# Sheet1.net
KiCad netlist of a schematic drawn in Altium Designer
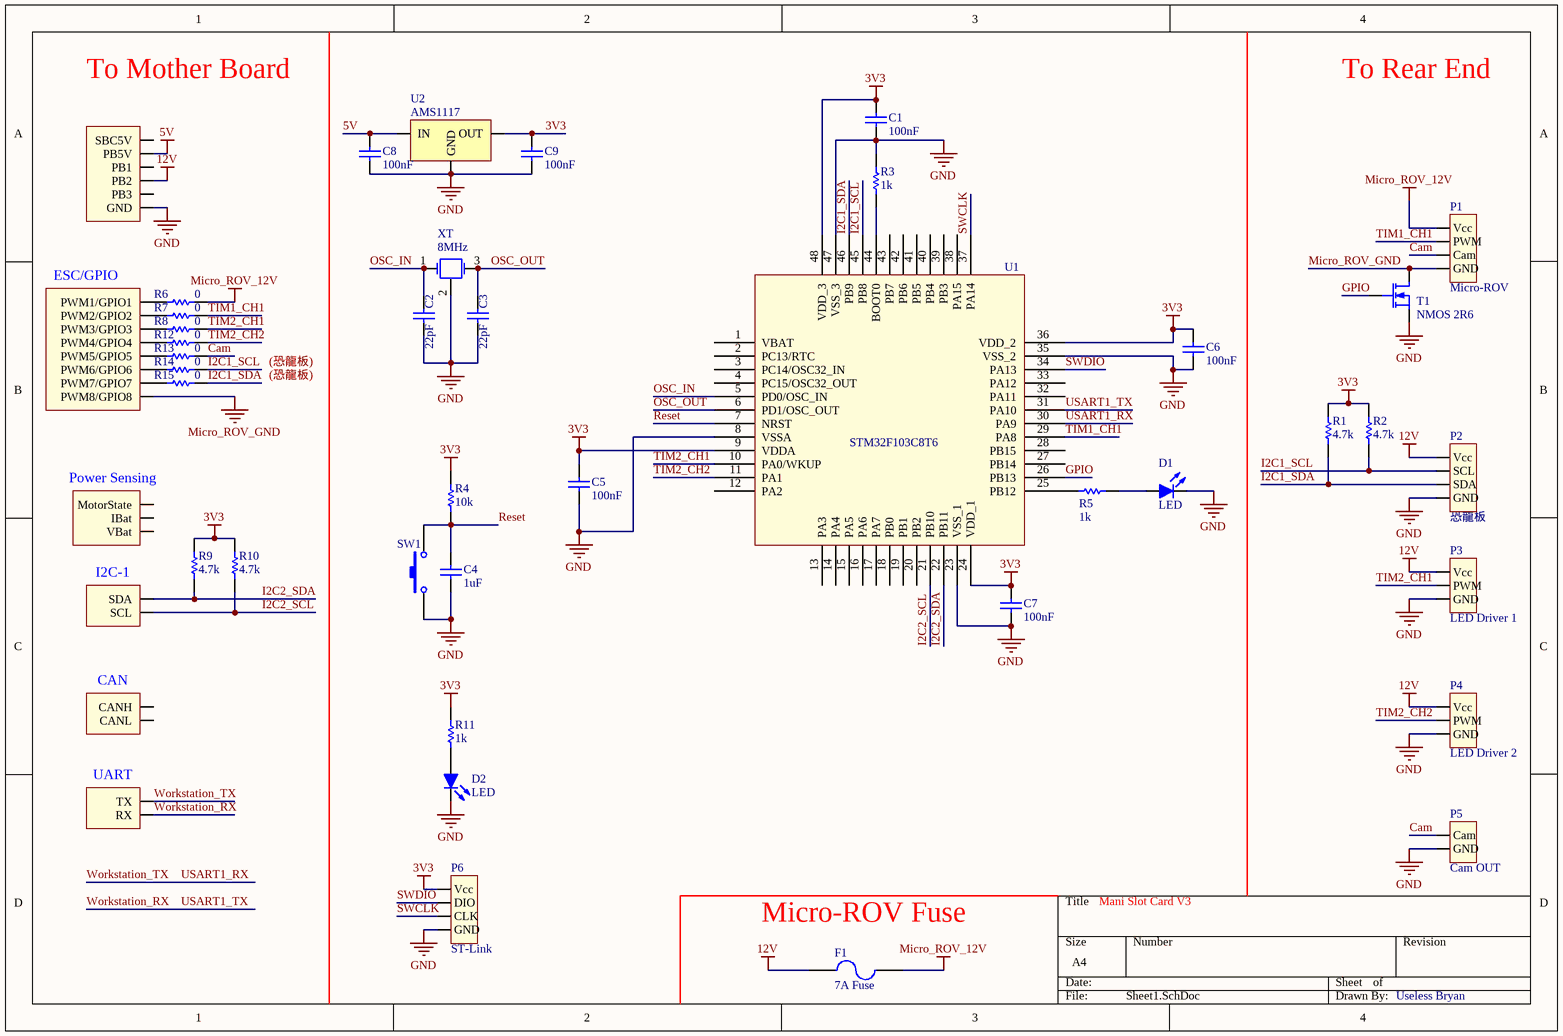
[diagram p0: Sheet1.SchDoc]

(export (version "E")
  (design (tool "Eeschema 10.0.6"))
  (components
    (comp (ref "C1") (value "100nF") (footprint "C0805") (libsource (lib "MyOwnSchlib_ver1.2") (part "Cap")))
    (comp (ref "C2") (value "22pF") (footprint "C0805") (libsource (lib "MyOwnSchlib_ver1.2") (part "Cap")))
    (comp (ref "C3") (value "22pF") (footprint "C0805") (libsource (lib "MyOwnSchlib_ver1.2") (part "Cap")))
    (comp (ref "C4") (value "1uF") (footprint "C0805") (libsource (lib "MyOwnSchlib_ver1.2") (part "Cap")))
    (comp (ref "C5") (value "100nF") (footprint "C0805") (libsource (lib "MyOwnSchlib_ver1.2") (part "Cap")))
    (comp (ref "C6") (value "100nF") (footprint "C0805") (libsource (lib "MyOwnSchlib_ver1.2") (part "Cap")))
    (comp (ref "C7") (value "100nF") (footprint "C0805") (libsource (lib "MyOwnSchlib_ver1.2") (part "Cap")))
    (comp (ref "C8") (value "100nF") (footprint "C0805") (libsource (lib "MyOwnSchlib_ver1.2") (part "Cap")))
    (comp (ref "C9") (value "100nF") (footprint "C0805") (libsource (lib "MyOwnSchlib_ver1.2") (part "Cap")))
    (comp (ref "Con1") (value "2x10pin") (footprint "2x10pin") (libsource (lib "Schlib1") (part "2x10pin")))
    (comp (ref "Con2") (value "2x6pin") (footprint "2x6pin") (libsource (lib "Schlib1") (part "2x6pin")))
    (comp (ref "D1") (value "LED") (footprint "LED-0805") (libsource (lib "MyOwnSchlib_ver1.2") (part "LED")))
    (comp (ref "D2") (value "LED") (footprint "LED-0805") (libsource (lib "MyOwnSchlib_ver1.2") (part "LED")))
    (comp (ref "F1")
      (value "7A Fuse")
      (footprint "FUSE-BLXA")
      (libsource (lib "MyOwnSchlib_ver1.2") (part "Fuse"))
    )
    (comp (ref "P1") (value "Micro-ROV") (footprint "XH2.54-4PIN_SMD") (libsource (lib "") (part "4Pin_2")))
    (comp (ref "P2")
      (value "Hung Lone V1")
      (footprint "XH2.54-4PIN_SMD")
      (libsource (lib "") (part "4Pin_1"))
    )
    (comp (ref "P3")
      (value "LED Driver 1")
      (footprint "XH2.54-3Pin_SMD")
      (libsource (lib "MyOwnSchlib_ver1.2") (part "3Pin"))
    )
    (comp (ref "P4")
      (value "LED Driver 2")
      (footprint "XH2.54-3Pin_SMD")
      (libsource (lib "MyOwnSchlib_ver1.2") (part "3Pin"))
    )
    (comp (ref "P5")
      (value "Cam OUT")
      (footprint "XH2.54-2Pin_SMD")
      (libsource (lib "MyOwnSchlib_ver1.2") (part "2Pin"))
    )
    (comp (ref "P6")
      (value "ST-Link")
      (footprint "XH2.54-4pin")
      (libsource (lib "MyOwnSchlib_ver1.2") (part "4Pin"))
    )
    (comp (ref "R1")
      (value "4.7k")
      (footprint "R0805")
      (description "pull-up resistor")
      (libsource (lib "MyOwnSchlib_ver1.2") (part "Resistor"))
    )
    (comp (ref "R2")
      (value "4.7k")
      (footprint "R0805")
      (description "pull-up resistor")
      (libsource (lib "MyOwnSchlib_ver1.2") (part "Resistor"))
    )
    (comp (ref "R3")
      (value "1k")
      (footprint "R0805")
      (libsource (lib "MyOwnSchlib_ver1.2") (part "Resistor"))
    )
    (comp (ref "R4")
      (value "10k")
      (footprint "R0805")
      (description "pull-up resistor")
      (libsource (lib "MyOwnSchlib_ver1.2") (part "Resistor"))
    )
    (comp (ref "R5")
      (value "1k")
      (footprint "R0805")
      (libsource (lib "MyOwnSchlib_ver1.2") (part "Resistor"))
    )
    (comp (ref "R6") (value "0") (footprint "R1206") (libsource (lib "MyOwnSchlib_ver1.2") (part "Resistor")))
    (comp (ref "R7") (value "0") (footprint "R0603") (libsource (lib "MyOwnSchlib_ver1.2") (part "Resistor")))
    (comp (ref "R8") (value "0") (footprint "R0603") (libsource (lib "MyOwnSchlib_ver1.2") (part "Resistor")))
    (comp (ref "R9")
      (value "4.7k")
      (footprint "R0805")
      (libsource (lib "MyOwnSchlib_ver1.2") (part "Resistor"))
    )
    (comp (ref "R10")
      (value "4.7k")
      (footprint "R0805")
      (libsource (lib "MyOwnSchlib_ver1.2") (part "Resistor"))
    )
    (comp (ref "R11")
      (value "1k")
      (footprint "R0805")
      (libsource (lib "MyOwnSchlib_ver1.2") (part "Resistor"))
    )
    (comp (ref "R12")
      (value "0")
      (footprint "R0603")
      (libsource (lib "MyOwnSchlib_ver1.2") (part "Resistor"))
    )
    (comp (ref "R13")
      (value "0")
      (footprint "R0603")
      (libsource (lib "MyOwnSchlib_ver1.2") (part "Resistor"))
    )
    (comp (ref "R14")
      (value "0")
      (footprint "R0603")
      (libsource (lib "MyOwnSchlib_ver1.2") (part "Resistor"))
    )
    (comp (ref "R15")
      (value "0")
      (footprint "R0603")
      (libsource (lib "MyOwnSchlib_ver1.2") (part "Resistor"))
    )
    (comp (ref "SW1")
      (value "SW-PB")
      (footprint "Switch-2pin")
      (libsource (lib "MyOwnSchlib_ver1.2") (part "SW-PB"))
    )
    (comp (ref "T1")
      (value "NMOS 2R6")
      (footprint "TPH2R608NH")
      (libsource (lib "convert") (part "MOSFET-N"))
    )
    (comp (ref "U1")
      (value "STM32F103C8T6")
      (footprint "LQFP48")
      (libsource (lib "MyOwnSchlib_ver1.2") (part "STM32F103C8T6"))
    )
    (comp (ref "U2")
      (value "AMS1117")
      (footprint "SOT-223")
      (libsource (lib "MyOwnSchlib_ver1.2") (part "AMS1117"))
    )
    (comp (ref "XT")
      (value "8MHz")
      (footprint "3225-P")
      (libsource (lib "MyOwnSchlib_ver1.2") (part "Passive Crystal"))
    )
  )
  (nets
    (net (code "1") (name "/Cam") (class "Default")
      (node (ref "P1") (pin "3") (pinfunction "Cam_3") (pintype "passive"))
      (node (ref "P5") (pin "1") (pinfunction "Cam_1") (pintype "passive"))
      (node (ref "R13") (pin "2") (pinfunction "2_2") (pintype "passive"))
    )
    (net (code "2") (name "/GPIO") (class "Default")
      (node (ref "T1") (pin "2") (pinfunction "G_2") (pintype "passive"))
      (node (ref "U1") (pin "26") (pinfunction "PB13_26") (pintype "passive"))
    )
    (net (code "3") (name "/I2C1_SCL") (class "Default")
      (node (ref "P2") (pin "2") (pinfunction "SCL_2") (pintype "passive"))
      (node (ref "R14") (pin "2") (pinfunction "2_2") (pintype "passive"))
      (node (ref "R2") (pin "1") (pinfunction "1_1") (pintype "passive"))
      (node (ref "U1") (pin "45") (pinfunction "PB8_45") (pintype "passive"))
    )
    (net (code "4") (name "/I2C1_SDA") (class "Default")
      (node (ref "P2") (pin "3") (pinfunction "SDA_3") (pintype "passive"))
      (node (ref "R1") (pin "1") (pinfunction "1_1") (pintype "passive"))
      (node (ref "R15") (pin "2") (pinfunction "2_2") (pintype "passive"))
      (node (ref "U1") (pin "46") (pinfunction "PB9_46") (pintype "passive"))
    )
    (net (code "5") (name "/I2C2_SCL") (class "Default")
      (node (ref "Con1") (pin "14") (pinfunction "SCL_14") (pintype "passive"))
      (node (ref "R10") (pin "1") (pinfunction "1_1") (pintype "passive"))
      (node (ref "U1") (pin "21") (pinfunction "PB10_21") (pintype "passive"))
    )
    (net (code "6") (name "/I2C2_SDA") (class "Default")
      (node (ref "Con1") (pin "13") (pinfunction "SDA_13") (pintype "passive"))
      (node (ref "R9") (pin "1") (pinfunction "1_1") (pintype "passive"))
      (node (ref "U1") (pin "22") (pinfunction "PB11_22") (pintype "passive"))
    )
    (net (code "7") (name "/OSC_IN") (class "Default")
      (node (ref "C2") (pin "2") (pinfunction "2_2") (pintype "passive"))
      (node (ref "U1") (pin "5") (pinfunction "PD0/OSC_IN_5") (pintype "passive"))
      (node (ref "XT") (pin "1") (pinfunction "OSC1_1") (pintype "passive"))
    )
    (net (code "8") (name "/OSC_OUT") (class "Default")
      (node (ref "C3") (pin "2") (pinfunction "2_2") (pintype "passive"))
      (node (ref "U1") (pin "6") (pinfunction "PD1/OSC_OUT_6") (pintype "passive"))
      (node (ref "XT") (pin "3") (pinfunction "OSC2_3") (pintype "passive"))
    )
    (net (code "9") (name "/Reset") (class "Default")
      (node (ref "C4") (pin "2") (pinfunction "2_2") (pintype "passive"))
      (node (ref "R4") (pin "1") (pinfunction "1_1") (pintype "passive"))
      (node (ref "SW1") (pin "2") (pinfunction "2_2") (pintype "passive"))
      (node (ref "U1") (pin "7") (pinfunction "NRST_7") (pintype "passive"))
    )
    (net (code "10") (name "/SWCLK") (class "Default")
      (node (ref "P6") (pin "3") (pinfunction "CLK_3") (pintype "passive"))
      (node (ref "U1") (pin "37") (pinfunction "PA14_37") (pintype "passive"))
    )
    (net (code "11") (name "/SWDIO") (class "Default")
      (node (ref "P6") (pin "2") (pinfunction "DIO_2") (pintype "passive"))
      (node (ref "U1") (pin "34") (pinfunction "PA13_34") (pintype "passive"))
    )
    (net (code "12") (name "/TIM1_CH1") (class "Default")
      (node (ref "P1") (pin "2") (pinfunction "PWM_2") (pintype "passive"))
      (node (ref "R7") (pin "2") (pinfunction "2_2") (pintype "passive"))
      (node (ref "U1") (pin "29") (pinfunction "PA8_29") (pintype "passive"))
    )
    (net (code "13") (name "/TIM2_CH1") (class "Default")
      (node (ref "P3") (pin "2") (pinfunction "PWM_2") (pintype "passive"))
      (node (ref "R8") (pin "2") (pinfunction "2_2") (pintype "passive"))
      (node (ref "U1") (pin "10") (pinfunction "PA0/WKUP_10") (pintype "passive"))
    )
    (net (code "14") (name "/TIM2_CH2") (class "Default")
      (node (ref "P4") (pin "2") (pinfunction "PWM_2") (pintype "passive"))
      (node (ref "R12") (pin "2") (pinfunction "2_2") (pintype "passive"))
      (node (ref "U1") (pin "11") (pinfunction "PA1_11") (pintype "passive"))
    )
    (net (code "15") (name "/USART1_RX") (class "Default")
      (node (ref "Con1") (pin "19") (pinfunction "TX_19") (pintype "passive"))
      (node (ref "U1") (pin "30") (pinfunction "PA9_30") (pintype "passive"))
    )
    (net (code "16") (name "/USART1_TX") (class "Default")
      (node (ref "Con1") (pin "20") (pinfunction "RX_20") (pintype "passive"))
      (node (ref "U1") (pin "31") (pinfunction "PA10_31") (pintype "passive"))
    )
    (net (code "17") (name "3V3") (class "Default")
      (node (ref "C1") (pin "2") (pinfunction "2_2") (pintype "passive"))
      (node (ref "C5") (pin "2") (pinfunction "2_2") (pintype "passive"))
      (node (ref "C6") (pin "2") (pinfunction "2_2") (pintype "passive"))
      (node (ref "C7") (pin "2") (pinfunction "2_2") (pintype "passive"))
      (node (ref "C9") (pin "2") (pinfunction "2_2") (pintype "passive"))
      (node (ref "P6") (pin "1") (pinfunction "Vcc_1") (pintype "passive"))
      (node (ref "R1") (pin "2") (pinfunction "2_2") (pintype "passive"))
      (node (ref "R10") (pin "2") (pinfunction "2_2") (pintype "passive"))
      (node (ref "R11") (pin "2") (pinfunction "2_2") (pintype "passive"))
      (node (ref "R2") (pin "2") (pinfunction "2_2") (pintype "passive"))
      (node (ref "R4") (pin "2") (pinfunction "2_2") (pintype "passive"))
      (node (ref "R9") (pin "2") (pinfunction "2_2") (pintype "passive"))
      (node (ref "U1") (pin "24") (pinfunction "VDD_1_24") (pintype "passive"))
      (node (ref "U1") (pin "36") (pinfunction "VDD_2_36") (pintype "passive"))
      (node (ref "U1") (pin "48") (pinfunction "VDD_3_48") (pintype "passive"))
      (node (ref "U1") (pin "9") (pinfunction "VDDA_9") (pintype "passive"))
      (node (ref "U2") (pin "2") (pinfunction "OUT_2") (pintype "passive"))
    )
    (net (code "18") (name "5V") (class "Default")
      (node (ref "C8") (pin "2") (pinfunction "2_2") (pintype "passive"))
      (node (ref "Con2") (pin "2") (pinfunction "PB5V_2") (pintype "passive"))
      (node (ref "U2") (pin "3") (pinfunction "IN_3") (pintype "passive"))
    )
    (net (code "19") (name "12V") (class "Default")
      (node (ref "Con2") (pin "4") (pinfunction "PB2_4") (pintype "passive"))
      (node (ref "F1") (pin "1") (pinfunction "1_1") (pintype "passive"))
      (node (ref "P2") (pin "1") (pinfunction "Vcc_1") (pintype "passive"))
      (node (ref "P3") (pin "1") (pinfunction "Vcc_1") (pintype "passive"))
      (node (ref "P4") (pin "1") (pinfunction "Vcc_1") (pintype "passive"))
    )
    (net (code "20") (name "GND") (class "Default")
      (node (ref "C1") (pin "1") (pinfunction "1_1") (pintype "passive"))
      (node (ref "C2") (pin "1") (pinfunction "1_1") (pintype "passive"))
      (node (ref "C3") (pin "1") (pinfunction "1_1") (pintype "passive"))
      (node (ref "C4") (pin "1") (pinfunction "1_1") (pintype "passive"))
      (node (ref "C5") (pin "1") (pinfunction "1_1") (pintype "passive"))
      (node (ref "C6") (pin "1") (pinfunction "1_1") (pintype "passive"))
      (node (ref "C7") (pin "1") (pinfunction "1_1") (pintype "passive"))
      (node (ref "C8") (pin "1") (pinfunction "1_1") (pintype "passive"))
      (node (ref "C9") (pin "1") (pinfunction "1_1") (pintype "passive"))
      (node (ref "Con2") (pin "6") (pinfunction "GND_6") (pintype "passive"))
      (node (ref "D1") (pin "2") (pinfunction "K_2") (pintype "passive"))
      (node (ref "D2") (pin "2") (pinfunction "K_2") (pintype "passive"))
      (node (ref "P2") (pin "4") (pinfunction "GND_4") (pintype "passive"))
      (node (ref "P3") (pin "3") (pinfunction "GND_3") (pintype "passive"))
      (node (ref "P4") (pin "3") (pinfunction "GND_3") (pintype "passive"))
      (node (ref "P5") (pin "2") (pinfunction "GND_2") (pintype "passive"))
      (node (ref "P6") (pin "4") (pinfunction "GND_4") (pintype "passive"))
      (node (ref "R3") (pin "2") (pinfunction "2_2") (pintype "passive"))
      (node (ref "SW1") (pin "1") (pinfunction "1_1") (pintype "passive"))
      (node (ref "T1") (pin "3") (pinfunction "S_3") (pintype "passive"))
      (node (ref "U1") (pin "23") (pinfunction "VSS_1_23") (pintype "passive"))
      (node (ref "U1") (pin "35") (pinfunction "VSS_2_35") (pintype "passive"))
      (node (ref "U1") (pin "47") (pinfunction "VSS_3_47") (pintype "passive"))
      (node (ref "U1") (pin "8") (pinfunction "VSSA_8") (pintype "passive"))
      (node (ref "U2") (pin "1") (pinfunction "GND_1") (pintype "passive"))
      (node (ref "XT") (pin "2") (pinfunction "2_2") (pintype "passive"))
    )
    (net (code "21") (name "Micro_ROV_12V") (class "Default")
      (node (ref "F1") (pin "2") (pinfunction "2_2") (pintype "passive"))
      (node (ref "P1") (pin "1") (pinfunction "Vcc_1") (pintype "passive"))
      (node (ref "R6") (pin "2") (pinfunction "2_2") (pintype "passive"))
    )
    (net (code "22") (name "Micro_ROV_GND") (class "Default")
      (node (ref "Con1") (pin "8") (pinfunction "PWM8/GPIO8_8") (pintype "passive"))
      (node (ref "P1") (pin "4") (pinfunction "GND_4") (pintype "passive"))
      (node (ref "T1") (pin "1") (pinfunction "D_1") (pintype "passive"))
    )
    (net (code "23") (name "Net-(Con1A-PWM1{slash}GPIO1)") (class "Default")
      (node (ref "Con1") (pin "1") (pinfunction "PWM1/GPIO1_1") (pintype "passive"))
      (node (ref "R6") (pin "1") (pinfunction "1_1") (pintype "passive"))
    )
    (net (code "24") (name "Net-(Con1A-PWM2{slash}GPIO2)") (class "Default")
      (node (ref "Con1") (pin "2") (pinfunction "PWM2/GPIO2_2") (pintype "passive"))
      (node (ref "R7") (pin "1") (pinfunction "1_1") (pintype "passive"))
    )
    (net (code "25") (name "Net-(Con1A-PWM3{slash}GPIO3)") (class "Default")
      (node (ref "Con1") (pin "3") (pinfunction "PWM3/GPIO3_3") (pintype "passive"))
      (node (ref "R8") (pin "1") (pinfunction "1_1") (pintype "passive"))
    )
    (net (code "26") (name "Net-(Con1A-PWM4{slash}GPIO4)") (class "Default")
      (node (ref "Con1") (pin "4") (pinfunction "PWM4/GPIO4_4") (pintype "passive"))
      (node (ref "R12") (pin "1") (pinfunction "1_1") (pintype "passive"))
    )
    (net (code "27") (name "Net-(Con1A-PWM5{slash}GPIO5)") (class "Default")
      (node (ref "Con1") (pin "5") (pinfunction "PWM5/GPIO5_5") (pintype "passive"))
      (node (ref "R13") (pin "1") (pinfunction "1_1") (pintype "passive"))
    )
    (net (code "28") (name "Net-(Con1A-PWM6{slash}GPIO6)") (class "Default")
      (node (ref "Con1") (pin "6") (pinfunction "PWM6/GPIO6_6") (pintype "passive"))
      (node (ref "R14") (pin "1") (pinfunction "1_1") (pintype "passive"))
    )
    (net (code "29") (name "Net-(Con1A-PWM7{slash}GPIO7)") (class "Default")
      (node (ref "Con1") (pin "7") (pinfunction "PWM7/GPIO7_7") (pintype "passive"))
      (node (ref "R15") (pin "1") (pinfunction "1_1") (pintype "passive"))
    )
    (net (code "30") (name "Net-(D1-A)") (class "Default")
      (node (ref "D1") (pin "1") (pinfunction "A_1") (pintype "passive"))
      (node (ref "R5") (pin "2") (pinfunction "2_2") (pintype "passive"))
    )
    (net (code "31") (name "Net-(D2-A)") (class "Default")
      (node (ref "D2") (pin "1") (pinfunction "A_1") (pintype "passive"))
      (node (ref "R11") (pin "1") (pinfunction "1_1") (pintype "passive"))
    )
    (net (code "32") (name "Net-(U1-BOOT0)") (class "Default")
      (node (ref "R3") (pin "1") (pinfunction "1_1") (pintype "passive"))
      (node (ref "U1") (pin "44") (pinfunction "BOOT0_44") (pintype "passive"))
    )
    (net (code "33") (name "Net-(U1-PB12)") (class "Default")
      (node (ref "R5") (pin "1") (pinfunction "1_1") (pintype "passive"))
      (node (ref "U1") (pin "25") (pinfunction "PB12_25") (pintype "passive"))
    )
    (net (code "34") (name "unconnected-(Con1B-IBat-Pad11)") (class "Default")
      (node (ref "Con1") (pin "11") (pinfunction "IBat_11") (pintype "passive"))
    )
    (net (code "35") (name "unconnected-(Con1B-MotorState-Pad10)") (class "Default")
      (node (ref "Con1") (pin "10") (pinfunction "MotorState_10") (pintype "passive"))
    )
    (net (code "36") (name "unconnected-(Con1B-VBat-Pad12)") (class "Default")
      (node (ref "Con1") (pin "12") (pinfunction "VBat_12") (pintype "passive"))
    )
    (net (code "37") (name "unconnected-(Con1D-CANH-Pad15)") (class "Default")
      (node (ref "Con1") (pin "15") (pinfunction "CANH_15") (pintype "passive"))
    )
    (net (code "38") (name "unconnected-(Con1D-CANL-Pad16)") (class "Default")
      (node (ref "Con1") (pin "16") (pinfunction "CANL_16") (pintype "passive"))
    )
    (net (code "39") (name "unconnected-(Con2-PB1-Pad3)") (class "Default")
      (node (ref "Con2") (pin "3") (pinfunction "PB1_3") (pintype "passive"))
    )
    (net (code "40") (name "unconnected-(Con2-PB3-Pad5)") (class "Default")
      (node (ref "Con2") (pin "5") (pinfunction "PB3_5") (pintype "passive"))
    )
    (net (code "41") (name "unconnected-(Con2-SBC5V-Pad1)") (class "Default")
      (node (ref "Con2") (pin "1") (pinfunction "SBC5V_1") (pintype "passive"))
    )
    (net (code "42") (name "unconnected-(U1-PA2-Pad12)") (class "Default")
      (node (ref "U1") (pin "12") (pinfunction "PA2_12") (pintype "passive"))
    )
    (net (code "43") (name "unconnected-(U1-PA3-Pad13)") (class "Default")
      (node (ref "U1") (pin "13") (pinfunction "PA3_13") (pintype "passive"))
    )
    (net (code "44") (name "unconnected-(U1-PA4-Pad14)") (class "Default")
      (node (ref "U1") (pin "14") (pinfunction "PA4_14") (pintype "passive"))
    )
    (net (code "45") (name "unconnected-(U1-PA5-Pad15)") (class "Default")
      (node (ref "U1") (pin "15") (pinfunction "PA5_15") (pintype "passive"))
    )
    (net (code "46") (name "unconnected-(U1-PA6-Pad16)") (class "Default")
      (node (ref "U1") (pin "16") (pinfunction "PA6_16") (pintype "passive"))
    )
    (net (code "47") (name "unconnected-(U1-PA7-Pad17)") (class "Default")
      (node (ref "U1") (pin "17") (pinfunction "PA7_17") (pintype "passive"))
    )
    (net (code "48") (name "unconnected-(U1-PA11-Pad32)") (class "Default")
      (node (ref "U1") (pin "32") (pinfunction "PA11_32") (pintype "passive"))
    )
    (net (code "49") (name "unconnected-(U1-PA12-Pad33)") (class "Default")
      (node (ref "U1") (pin "33") (pinfunction "PA12_33") (pintype "passive"))
    )
    (net (code "50") (name "unconnected-(U1-PA15-Pad38)") (class "Default")
      (node (ref "U1") (pin "38") (pinfunction "PA15_38") (pintype "passive"))
    )
    (net (code "51") (name "unconnected-(U1-PB0-Pad18)") (class "Default")
      (node (ref "U1") (pin "18") (pinfunction "PB0_18") (pintype "passive"))
    )
    (net (code "52") (name "unconnected-(U1-PB1-Pad19)") (class "Default")
      (node (ref "U1") (pin "19") (pinfunction "PB1_19") (pintype "passive"))
    )
    (net (code "53") (name "unconnected-(U1-PB2-Pad20)") (class "Default")
      (node (ref "U1") (pin "20") (pinfunction "PB2_20") (pintype "passive"))
    )
    (net (code "54") (name "unconnected-(U1-PB3-Pad39)") (class "Default")
      (node (ref "U1") (pin "39") (pinfunction "PB3_39") (pintype "passive"))
    )
    (net (code "55") (name "unconnected-(U1-PB4-Pad40)") (class "Default")
      (node (ref "U1") (pin "40") (pinfunction "PB4_40") (pintype "passive"))
    )
    (net (code "56") (name "unconnected-(U1-PB5-Pad41)") (class "Default")
      (node (ref "U1") (pin "41") (pinfunction "PB5_41") (pintype "passive"))
    )
    (net (code "57") (name "unconnected-(U1-PB6-Pad42)") (class "Default")
      (node (ref "U1") (pin "42") (pinfunction "PB6_42") (pintype "passive"))
    )
    (net (code "58") (name "unconnected-(U1-PB7-Pad43)") (class "Default")
      (node (ref "U1") (pin "43") (pinfunction "PB7_43") (pintype "passive"))
    )
    (net (code "59") (name "unconnected-(U1-PB14-Pad27)") (class "Default")
      (node (ref "U1") (pin "27") (pinfunction "PB14_27") (pintype "passive"))
    )
    (net (code "60") (name "unconnected-(U1-PB15-Pad28)") (class "Default")
      (node (ref "U1") (pin "28") (pinfunction "PB15_28") (pintype "passive"))
    )
    (net (code "61") (name "unconnected-(U1-PC13{slash}RTC-Pad2)") (class "Default")
      (node (ref "U1") (pin "2") (pinfunction "PC13/RTC_2") (pintype "passive"))
    )
    (net (code "62") (name "unconnected-(U1-PC14{slash}OSC32_IN-Pad3)") (class "Default")
      (node (ref "U1") (pin "3") (pinfunction "PC14/OSC32_IN_3") (pintype "passive"))
    )
    (net (code "63") (name "unconnected-(U1-PC15{slash}OSC32_OUT-Pad4)") (class "Default")
      (node (ref "U1") (pin "4") (pinfunction "PC15/OSC32_OUT_4") (pintype "passive"))
    )
    (net (code "64") (name "unconnected-(U1-VBAT-Pad1)") (class "Default")
      (node (ref "U1") (pin "1") (pinfunction "VBAT_1") (pintype "passive"))
    )
  )
)
